# main.net
KiCad netlist of a schematic drawn in Altium Designer
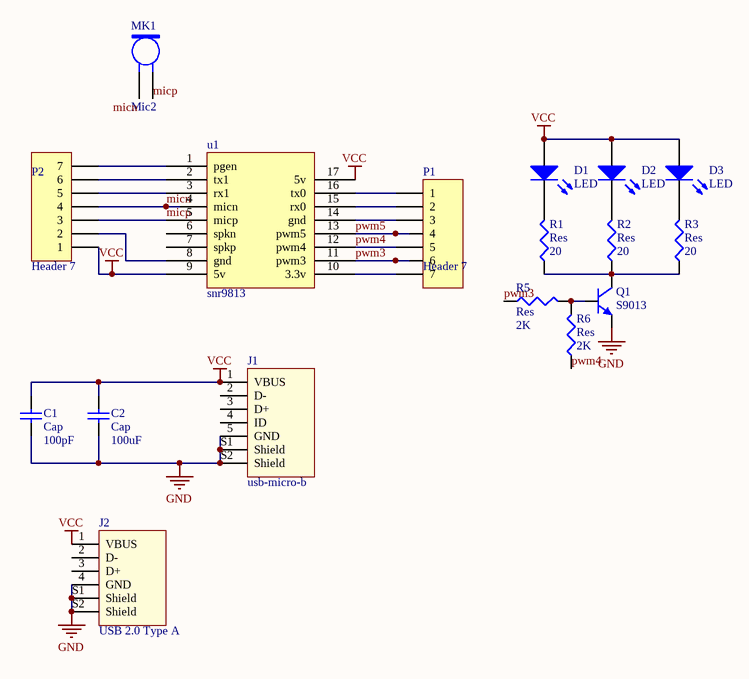
[diagram p0: main.SchDoc]

(export (version "E")
  (design (tool "Eeschema 10.0.6"))
  (components
    (comp (ref "C1")
      (value "Cap")
      (footprint "C0805_N")
      (description "Capacitor")
      (fields (field (name "ALTIUM_VALUE") "100pF") (field (name "PUBLISHER") "Altium Limited"))
      (libsource (lib "General") (part "Cap"))
    )
    (comp (ref "C2")
      (value "Cap")
      (footprint "C0805_N")
      (description "Capacitor")
      (fields (field (name "ALTIUM_VALUE") "100uF") (field (name "PUBLISHER") "Altium Limited"))
      (libsource (lib "General") (part "Cap"))
    )
    (comp (ref "D1")
      (value "LED")
      (footprint "LED3528")
      (description "Typical LED")
      (fields (field (name "PUBLISHER") "Altium Limited"))
      (libsource (lib "General") (part "LED"))
    )
    (comp (ref "D2")
      (value "LED")
      (footprint "LED3528")
      (description "Typical LED")
      (fields (field (name "PUBLISHER") "Altium Limited"))
      (libsource (lib "General") (part "LED"))
    )
    (comp (ref "D3")
      (value "LED")
      (footprint "LED3528")
      (description "Typical LED")
      (fields (field (name "PUBLISHER") "Altium Limited"))
      (libsource (lib "General") (part "LED"))
    )
    (comp (ref "J1")
      (value "usb-micro-b")
      (footprint "usb-micro-b")
      (libsource (lib "snr9813") (part "usb-micro-b"))
    )
    (comp (ref "J2")
      (value "USB 2.0 Type A")
      (footprint "usb-a-mail")
      (libsource (lib "snr9813") (part "usb-a-male"))
    )
    (comp (ref "MK1")
      (value "Mic2")
      (footprint "PIN2")
      (description "Microphone")
      (fields (field (name "PUBLISHER") "Altium Limited"))
      (libsource (lib "Miscellaneous Devices") (part "Mic2"))
    )
    (comp (ref "P1")
      (value "Header 7")
      (footprint "HDR1X7")
      (description "Header, 7-Pin")
      (fields (field (name "PUBLISHER") "Altium Limited"))
      (libsource (lib "Miscellaneous Connectors") (part "Header 7"))
    )
    (comp (ref "P2")
      (value "Header 7")
      (footprint "HDR1X7")
      (description "Header, 7-Pin")
      (fields (field (name "PUBLISHER") "Altium Limited"))
      (libsource (lib "") (part "Header 7_1"))
    )
    (comp (ref "Q1")
      (value "NPN")
      (footprint "SOT23-3_L")
      (description "NPN General Purpose Amplifier")
      (fields (field (name "MODEL") "S9013"))
      (libsource (lib "General") (part "NPN"))
    )
    (comp (ref "R1")
      (value "Res")
      (footprint "R0805_L")
      (description "Resistor")
      (fields (field (name "ALTIUM_VALUE") "20") (field (name "PUBLISHER") "Altium Limited"))
      (libsource (lib "General") (part "Res"))
    )
    (comp (ref "R2")
      (value "Res")
      (footprint "R0805_L")
      (description "Resistor")
      (fields (field (name "ALTIUM_VALUE") "20") (field (name "PUBLISHER") "Altium Limited"))
      (libsource (lib "General") (part "Res"))
    )
    (comp (ref "R3")
      (value "Res")
      (footprint "R0805_L")
      (description "Resistor")
      (fields (field (name "ALTIUM_VALUE") "20") (field (name "PUBLISHER") "Altium Limited"))
      (libsource (lib "General") (part "Res"))
    )
    (comp (ref "R5")
      (value "Res")
      (footprint "R0805_M")
      (description "Resistor")
      (fields (field (name "ALTIUM_VALUE") "2K") (field (name "PUBLISHER") "Altium Limited"))
      (libsource (lib "General") (part "Res"))
    )
    (comp (ref "R6")
      (value "Res")
      (footprint "R0805_M")
      (description "Resistor")
      (fields (field (name "ALTIUM_VALUE") "2K") (field (name "PUBLISHER") "Altium Limited"))
      (libsource (lib "General") (part "Res"))
    )
    (comp (ref "u1") (value "snr9813") (footprint "SNR9813M17") (libsource (lib "snr9813") (part "snr9813")))
  )
  (nets
    (net (code "1") (name "/micn") (class "Default")
      (node (ref "MK1") (pin "1") (pinfunction "1_1") (pintype "passive"))
      (node (ref "P2") (pin "4") (pinfunction "4_4") (pintype "passive"))
      (node (ref "u1") (pin "4") (pinfunction "micn_4") (pintype "passive"))
    )
    (net (code "2") (name "/micp") (class "Default")
      (node (ref "MK1") (pin "2") (pinfunction "2_2") (pintype "passive"))
      (node (ref "P2") (pin "3") (pinfunction "3_3") (pintype "passive"))
      (node (ref "u1") (pin "5") (pinfunction "micp_5") (pintype "passive"))
    )
    (net (code "3") (name "/pwm3") (class "Default")
      (node (ref "P1") (pin "6") (pinfunction "6_6") (pintype "passive"))
      (node (ref "R5") (pin "1") (pinfunction "1_1") (pintype "passive"))
      (node (ref "u1") (pin "11") (pinfunction "pwm3_11") (pintype "passive"))
    )
    (net (code "4") (name "/pwm4") (class "Default")
      (node (ref "P1") (pin "5") (pinfunction "5_5") (pintype "passive"))
      (node (ref "R6") (pin "1") (pinfunction "1_1") (pintype "passive"))
      (node (ref "u1") (pin "12") (pinfunction "pwm4_12") (pintype "passive"))
    )
    (net (code "5") (name "/pwm5") (class "Default")
      (node (ref "P1") (pin "4") (pinfunction "4_4") (pintype "passive"))
      (node (ref "u1") (pin "13") (pinfunction "pwm5_13") (pintype "passive"))
    )
    (net (code "6") (name "GND") (class "Default")
      (node (ref "C1") (pin "1") (pinfunction "1_1") (pintype "passive"))
      (node (ref "C2") (pin "1") (pinfunction "1_1") (pintype "passive"))
      (node (ref "J1") (pin "5") (pinfunction "GND_5") (pintype "passive"))
      (node (ref "J1") (pin "S1") (pinfunction "Shield_S1") (pintype "passive"))
      (node (ref "J1") (pin "S2") (pinfunction "Shield_S2") (pintype "passive"))
      (node (ref "J2") (pin "4") (pinfunction "GND_4") (pintype "passive"))
      (node (ref "J2") (pin "S1") (pinfunction "Shield_S1") (pintype "passive"))
      (node (ref "J2") (pin "S2") (pinfunction "Shield_S2") (pintype "passive"))
      (node (ref "Q1") (pin "2") (pinfunction "E_2") (pintype "passive"))
    )
    (net (code "7") (name "Net-(D1-K)") (class "Default")
      (node (ref "D1") (pin "2") (pinfunction "K_2") (pintype "passive"))
      (node (ref "R1") (pin "2") (pinfunction "2_2") (pintype "passive"))
    )
    (net (code "8") (name "Net-(D2-K)") (class "Default")
      (node (ref "D2") (pin "2") (pinfunction "K_2") (pintype "passive"))
      (node (ref "R2") (pin "2") (pinfunction "2_2") (pintype "passive"))
    )
    (net (code "9") (name "Net-(D3-K)") (class "Default")
      (node (ref "D3") (pin "2") (pinfunction "K_2") (pintype "passive"))
      (node (ref "R3") (pin "2") (pinfunction "2_2") (pintype "passive"))
    )
    (net (code "10") (name "Net-(P1-Pad3)") (class "Default")
      (node (ref "P1") (pin "3") (pinfunction "3_3") (pintype "passive"))
      (node (ref "u1") (pin "14") (pinfunction "gnd_14") (pintype "passive"))
    )
    (net (code "11") (name "Net-(P2-Pad2)") (class "Default")
      (node (ref "P2") (pin "2") (pinfunction "2_2") (pintype "passive"))
      (node (ref "u1") (pin "8") (pinfunction "gnd_8") (pintype "passive"))
    )
    (net (code "12") (name "Net-(Q1-B)") (class "Default")
      (node (ref "Q1") (pin "1") (pinfunction "B_1") (pintype "passive"))
      (node (ref "R5") (pin "2") (pinfunction "2_2") (pintype "passive"))
      (node (ref "R6") (pin "2") (pinfunction "2_2") (pintype "passive"))
    )
    (net (code "13") (name "Net-(Q1-C)") (class "Default")
      (node (ref "Q1") (pin "3") (pinfunction "C_3") (pintype "passive"))
      (node (ref "R1") (pin "1") (pinfunction "1_1") (pintype "passive"))
      (node (ref "R2") (pin "1") (pinfunction "1_1") (pintype "passive"))
      (node (ref "R3") (pin "1") (pinfunction "1_1") (pintype "passive"))
    )
    (net (code "14") (name "Net-(u1-3.3v)") (class "Default")
      (node (ref "P1") (pin "7") (pinfunction "7_7") (pintype "passive"))
      (node (ref "u1") (pin "10") (pinfunction "3.3v_10") (pintype "passive"))
    )
    (net (code "15") (name "Net-(u1-pgen)") (class "Default")
      (node (ref "P2") (pin "7") (pinfunction "7_7") (pintype "passive"))
      (node (ref "u1") (pin "1") (pinfunction "pgen_1") (pintype "passive"))
    )
    (net (code "16") (name "Net-(u1-rx0)") (class "Default")
      (node (ref "P1") (pin "2") (pinfunction "2_2") (pintype "passive"))
      (node (ref "u1") (pin "15") (pinfunction "rx0_15") (pintype "passive"))
    )
    (net (code "17") (name "Net-(u1-rx1)") (class "Default")
      (node (ref "P2") (pin "5") (pinfunction "5_5") (pintype "passive"))
      (node (ref "u1") (pin "3") (pinfunction "rx1_3") (pintype "passive"))
    )
    (net (code "18") (name "Net-(u1-tx0)") (class "Default")
      (node (ref "P1") (pin "1") (pinfunction "1_1") (pintype "passive"))
      (node (ref "u1") (pin "16") (pinfunction "tx0_16") (pintype "passive"))
    )
    (net (code "19") (name "Net-(u1-tx1)") (class "Default")
      (node (ref "P2") (pin "6") (pinfunction "6_6") (pintype "passive"))
      (node (ref "u1") (pin "2") (pinfunction "tx1_2") (pintype "passive"))
    )
    (net (code "20") (name "VCC") (class "Default")
      (node (ref "C1") (pin "2") (pinfunction "2_2") (pintype "passive"))
      (node (ref "C2") (pin "2") (pinfunction "2_2") (pintype "passive"))
      (node (ref "D1") (pin "1") (pinfunction "A_1") (pintype "passive"))
      (node (ref "D2") (pin "1") (pinfunction "A_1") (pintype "passive"))
      (node (ref "D3") (pin "1") (pinfunction "A_1") (pintype "passive"))
      (node (ref "J1") (pin "1") (pinfunction "VBUS_1") (pintype "passive"))
      (node (ref "J2") (pin "1") (pinfunction "VBUS_1") (pintype "passive"))
      (node (ref "P2") (pin "1") (pinfunction "1_1") (pintype "passive"))
      (node (ref "u1") (pin "17") (pinfunction "5v_17") (pintype "passive"))
      (node (ref "u1") (pin "9") (pinfunction "5v_9") (pintype "passive"))
    )
    (net (code "21") (name "unconnected-(J1-D+-Pad3)") (class "Default")
      (node (ref "J1") (pin "3") (pinfunction "D+_3") (pintype "passive"))
    )
    (net (code "22") (name "unconnected-(J1-D--Pad2)") (class "Default")
      (node (ref "J1") (pin "2") (pinfunction "D-_2") (pintype "passive"))
    )
    (net (code "23") (name "unconnected-(J1-ID-Pad4)") (class "Default")
      (node (ref "J1") (pin "4") (pinfunction "ID_4") (pintype "passive"))
    )
    (net (code "24") (name "unconnected-(J2-D+-Pad3)") (class "Default")
      (node (ref "J2") (pin "3") (pinfunction "D+_3") (pintype "passive"))
    )
    (net (code "25") (name "unconnected-(J2-D--Pad2)") (class "Default")
      (node (ref "J2") (pin "2") (pinfunction "D-_2") (pintype "passive"))
    )
    (net (code "26") (name "unconnected-(u1-spkn-Pad6)") (class "Default")
      (node (ref "u1") (pin "6") (pinfunction "spkn_6") (pintype "passive"))
    )
    (net (code "27") (name "unconnected-(u1-spkp-Pad7)") (class "Default")
      (node (ref "u1") (pin "7") (pinfunction "spkp_7") (pintype "passive"))
    )
  )
)
